# dual_dcdc_converter.net
KiCad netlist of a schematic drawn in EasyEDA Pro
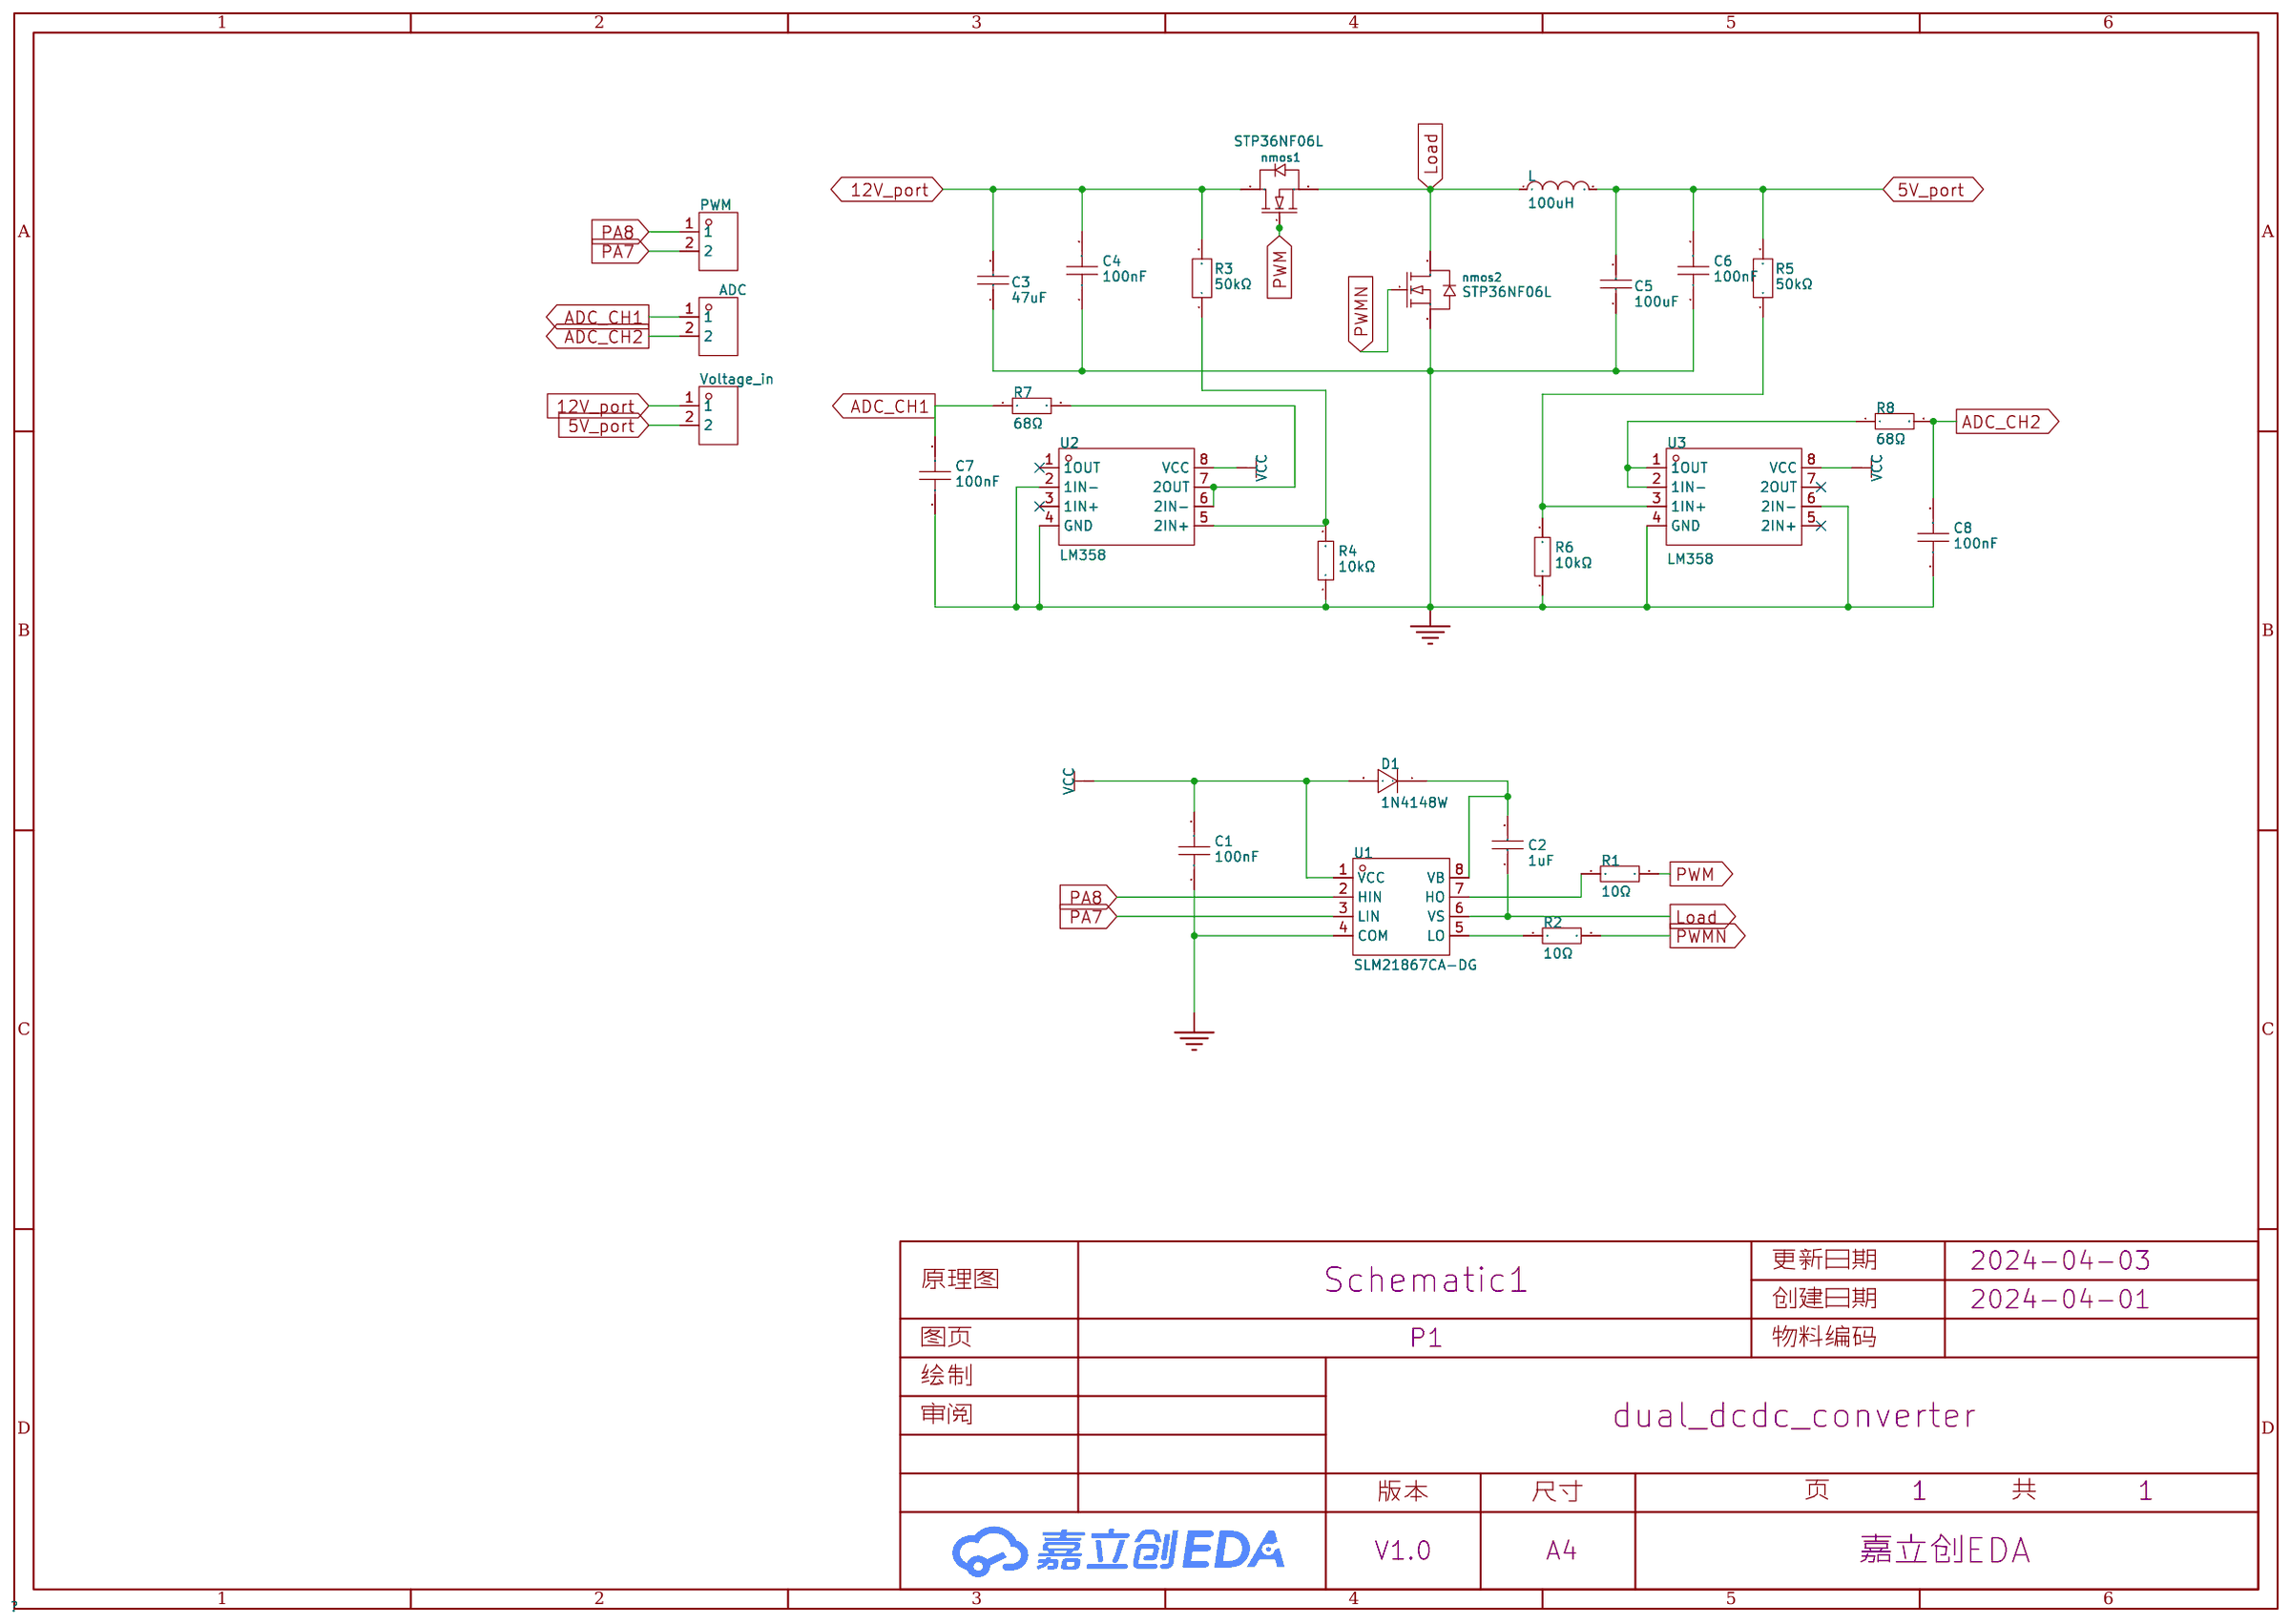
[diagram p0: schematic sheet]

(export (version "E")
  (design (tool "Eeschema 10.0.6"))
  (components
    (comp (ref "ADC")
      (value "FFH25405-S02S1001K6K")
      (footprint "easyedapro:HDR-TH_2P-P2.54-V-F_FFH25405")
      (fields (field (name "Manufacturer") "TXGA(特思嘉)"))
      (libsource (lib "easyedapro") (part "FFH25405-S02S1001K6K"))
    )
    (comp (ref "C1")
      (value "100nF")
      (footprint "easyedapro:C0603")
      (description "容值:100nF;精度:±10%;额定电压:50V;材质(温度系数):X7R;")
      (fields
        (field (name "Manufacturer Part") "CC0603KRX7R9BB104")
        (field (name "Manufacturer") "YAGEO(国巨)")
      )
      (libsource (lib "easyedapro") (part "CC0603KRX7R9BB104"))
    )
    (comp (ref "C2")
      (value "1uF")
      (footprint "easyedapro:C0805")
      (description "容值:1uF;精度:±10%;额定电压:50V;材质(温度系数):X7R;")
      (fields
        (field (name "Manufacturer Part") "CL21B105KBFNNNE")
        (field (name "Manufacturer") "SAMSUNG(三星)")
      )
      (libsource (lib "easyedapro") (part "CL21B105KBFNNNE"))
    )
    (comp (ref "C3")
      (value "47uF")
      (footprint "easyedapro:C0805")
      (description "容值:47uF;精度:±20%;额定电压:6.3V;材质(温度系数):X5R;")
      (fields
        (field (name "Manufacturer Part") "CL21A476MQYNNNE")
        (field (name "Manufacturer") "SAMSUNG(三星)")
      )
      (libsource (lib "easyedapro") (part "CL21A476MQYNNNE"))
    )
    (comp (ref "C4")
      (value "100nF")
      (footprint "easyedapro:C0603")
      (description "容值:100nF;精度:±10%;额定电压:50V;材质(温度系数):X7R;")
      (fields
        (field (name "Manufacturer Part") "CC0603KRX7R9BB104")
        (field (name "Manufacturer") "YAGEO(国巨)")
      )
      (libsource (lib "easyedapro") (part "CC0603KRX7R9BB104"))
    )
    (comp (ref "C5")
      (value "100uF")
      (footprint "easyedapro:C1206")
      (description "容值:100uF;精度:±20%;额定电压:6.3V;材质(温度系数):X5R;")
      (fields
        (field (name "Manufacturer Part") "CL31A107MQHNNNE")
        (field (name "Manufacturer") "SAMSUNG(三星)")
      )
      (libsource (lib "easyedapro") (part "CL31A107MQHNNNE"))
    )
    (comp (ref "C6")
      (value "100nF")
      (footprint "easyedapro:C0603")
      (description "容值:100nF;精度:±10%;额定电压:50V;材质(温度系数):X7R;")
      (fields
        (field (name "Manufacturer Part") "CC0603KRX7R9BB104")
        (field (name "Manufacturer") "YAGEO(国巨)")
      )
      (libsource (lib "easyedapro") (part "CC0603KRX7R9BB104"))
    )
    (comp (ref "C7")
      (value "100nF")
      (footprint "easyedapro:C0603")
      (description "容值:100nF;精度:±10%;额定电压:50V;材质(温度系数):X7R;")
      (fields
        (field (name "Manufacturer Part") "CC0603KRX7R9BB104")
        (field (name "Manufacturer") "YAGEO(国巨)")
      )
      (libsource (lib "easyedapro") (part "CC0603KRX7R9BB104"))
    )
    (comp (ref "C8")
      (value "100nF")
      (footprint "easyedapro:C0603")
      (description "容值:100nF;精度:±10%;额定电压:50V;材质(温度系数):X7R;")
      (fields
        (field (name "Manufacturer Part") "CC0603KRX7R9BB104")
        (field (name "Manufacturer") "YAGEO(国巨)")
      )
      (libsource (lib "easyedapro") (part "CC0603KRX7R9BB104"))
    )
    (comp (ref "D1")
      (value "1N4148W")
      (footprint "easyedapro:SOD-123F_L2.7-W1.6-LS3.8-RD")
      (description "二极管配置:独立式;正向压降(Vf):1V@50mA;直流反向耐压(Vr):75V;平均整流电流(Io):150mA;功率:400mW;反向恢复时间(trr):4ns;")
      (fields (field (name "Manufacturer") "ST(先科)"))
      (libsource (lib "easyedapro") (part "1N4148W_C81598"))
    )
    (comp (ref "L")
      (value "100uH")
      (footprint "easyedapro:IND-SMD_L10.5-W10.5")
      (description "电感值:100uH;精度:±20%;额定电流:1.35A;直流电阻(DCR):340mΩ;")
      (fields (field (name "Manufacturer Part") "CYL104R-100UH") (field (name "Manufacturer") "SHOU HAN(首韩)"))
      (libsource (lib "easyedapro") (part "CYL104R-100UH"))
    )
    (comp (ref "nmos1")
      (value "STP36NF06L")
      (footprint "easyedapro:TO-220-3_L10.0-W4.5-P2.54-L")
      (fields (field (name "Manufacturer") "ST(意法半导体)"))
      (libsource (lib "easyedapro") (part "STP36NF06L"))
    )
    (comp (ref "nmos2")
      (value "STP36NF06L")
      (footprint "easyedapro:TO-220-3_L10.0-W4.5-P2.54-L")
      (fields (field (name "Manufacturer") "ST(意法半导体)"))
      (libsource (lib "easyedapro") (part "STP36NF06L"))
    )
    (comp (ref "PWM")
      (value "FFH25405-S02S1001K6K")
      (footprint "easyedapro:HDR-TH_2P-P2.54-V-F_FFH25405")
      (fields (field (name "Manufacturer") "TXGA(特思嘉)"))
      (libsource (lib "easyedapro") (part "FFH25405-S02S1001K6K"))
    )
    (comp (ref "R1")
      (value "10Ω")
      (footprint "easyedapro:R0603")
      (description "电阻类型:厚膜电阻;阻值:10Ω;精度:±1%;功率:100mW;最大工作电压:75V;温度系数:±400ppm/°C;")
      (fields
        (field (name "Manufacturer Part") "0603WAF100JT5E")
        (field (name "Manufacturer") "UNI-ROYAL(厚声)")
      )
      (libsource (lib "easyedapro") (part "0603WAF100JT5E"))
    )
    (comp (ref "R2")
      (value "10Ω")
      (footprint "easyedapro:R0603")
      (description "电阻类型:厚膜电阻;阻值:10Ω;精度:±1%;功率:100mW;最大工作电压:75V;温度系数:±400ppm/°C;")
      (fields
        (field (name "Manufacturer Part") "0603WAF100JT5E")
        (field (name "Manufacturer") "UNI-ROYAL(厚声)")
      )
      (libsource (lib "easyedapro") (part "0603WAF100JT5E"))
    )
    (comp (ref "R3")
      (value "50kΩ")
      (footprint "easyedapro:R0805")
      (description "电阻类型:薄膜电阻;阻值:50kΩ;精度:±0.5%;功率:125mW;最大工作电压:150V;温度系数:±25ppm/°C;")
      (fields (field (name "Manufacturer Part") "ARG05DTC5002") (field (name "Manufacturer") "Viking(光颉)"))
      (libsource (lib "easyedapro") (part "ARG05DTC5002"))
    )
    (comp (ref "R4")
      (value "10kΩ")
      (footprint "easyedapro:R0603")
      (description "电阻类型:厚膜电阻;阻值:10kΩ;精度:±1%;功率:100mW;最大工作电压:75V;温度系数:±100ppm/°C;")
      (fields
        (field (name "Manufacturer Part") "0603WAF1002T5E")
        (field (name "Manufacturer") "UNI-ROYAL(厚声)")
      )
      (libsource (lib "easyedapro") (part "0603WAF1002T5E"))
    )
    (comp (ref "R5")
      (value "50kΩ")
      (footprint "easyedapro:R0805")
      (description "电阻类型:薄膜电阻;阻值:50kΩ;精度:±0.5%;功率:125mW;最大工作电压:150V;温度系数:±25ppm/°C;")
      (fields (field (name "Manufacturer Part") "ARG05DTC5002") (field (name "Manufacturer") "Viking(光颉)"))
      (libsource (lib "easyedapro") (part "ARG05DTC5002"))
    )
    (comp (ref "R6")
      (value "10kΩ")
      (footprint "easyedapro:R0603")
      (description "电阻类型:厚膜电阻;阻值:10kΩ;精度:±1%;功率:100mW;最大工作电压:75V;温度系数:±100ppm/°C;")
      (fields
        (field (name "Manufacturer Part") "0603WAF1002T5E")
        (field (name "Manufacturer") "UNI-ROYAL(厚声)")
      )
      (libsource (lib "easyedapro") (part "0603WAF1002T5E"))
    )
    (comp (ref "R7")
      (value "68Ω")
      (footprint "easyedapro:R0805")
      (description "电阻类型:厚膜电阻;阻值:68Ω;精度:±1%;功率:125mW;最大工作电压:150V;温度系数:±200ppm/°C;")
      (fields
        (field (name "Manufacturer Part") "0805W8F680JT5E")
        (field (name "Manufacturer") "UNI-ROYAL(厚声)")
      )
      (libsource (lib "easyedapro") (part "0805W8F680JT5E"))
    )
    (comp (ref "R8")
      (value "68Ω")
      (footprint "easyedapro:R0805")
      (description "电阻类型:厚膜电阻;阻值:68Ω;精度:±1%;功率:125mW;最大工作电压:150V;温度系数:±200ppm/°C;")
      (fields
        (field (name "Manufacturer Part") "0805W8F680JT5E")
        (field (name "Manufacturer") "UNI-ROYAL(厚声)")
      )
      (libsource (lib "easyedapro") (part "0805W8F680JT5E"))
    )
    (comp (ref "U1")
      (value "SLM21867CA-DG")
      (footprint "easyedapro:SOIC-8_L4.9-W3.9-P1.27-LS6.0-BL")
      (description "驱动通道数:2;峰值灌电流:2.5A;峰值拉电流:3A;电源电压:7V~20V;是否隔离:非隔离;")
      (fields (field (name "Manufacturer") "Sillumin(数明半导体)"))
      (libsource (lib "easyedapro") (part "SLM21867CA-DG"))
    )
    (comp (ref "U2")
      (value "LM358")
      (footprint "easyedapro:SOP-8_L5.0-W4.0-P1.27-LS6.0-BL")
      (description "放大器数:-;输入失调电压(Vos):9V;带宽(-3db):1MHz;")
      (fields (field (name "Manufacturer") "IDCHIP(英锐芯)"))
      (libsource (lib "easyedapro") (part "LM358_C329455"))
    )
    (comp (ref "U3")
      (value "LM358")
      (footprint "easyedapro:SOP-8_L5.0-W4.0-P1.27-LS6.0-BL")
      (description "放大器数:-;输入失调电压(Vos):9V;带宽(-3db):1MHz;")
      (fields (field (name "Manufacturer") "IDCHIP(英锐芯)"))
      (libsource (lib "easyedapro") (part "LM358_C329455"))
    )
    (comp (ref "Voltage_in")
      (value "FFH25405-S02S1001K6K")
      (footprint "easyedapro:HDR-TH_2P-P2.54-V-F_FFH25405")
      (fields (field (name "Manufacturer") "TXGA(特思嘉)"))
      (libsource (lib "easyedapro") (part "FFH25405-S02S1001K6K"))
    )
  )
  (nets
    (net (code "1") (name "5V_port") (class "Default")
      (node (ref "C5") (pin "2") (pinfunction "2_2") (pintype "input"))
      (node (ref "C6") (pin "2") (pinfunction "2_2") (pintype "unspecified"))
      (node (ref "L") (pin "2") (pinfunction "2_2") (pintype "unspecified"))
      (node (ref "R5") (pin "2") (pinfunction "2_2") (pintype "unspecified"))
      (node (ref "Voltage_in") (pin "2") (pinfunction "2_2") (pintype "unspecified"))
    )
    (net (code "2") (name "12V_port") (class "Default")
      (node (ref "C3") (pin "2") (pinfunction "2_2") (pintype "input"))
      (node (ref "C4") (pin "2") (pinfunction "2_2") (pintype "unspecified"))
      (node (ref "R3") (pin "2") (pinfunction "2_2") (pintype "unspecified"))
      (node (ref "Voltage_in") (pin "1") (pinfunction "1_1") (pintype "unspecified"))
      (node (ref "nmos1") (pin "2") (pinfunction "D_2") (pintype "input"))
    )
    (net (code "3") (name "ADC_CH1") (class "Default")
      (node (ref "ADC") (pin "1") (pinfunction "1_1") (pintype "unspecified"))
      (node (ref "C7") (pin "2") (pinfunction "2_2") (pintype "unspecified"))
      (node (ref "R7") (pin "1") (pinfunction "1_1") (pintype "input"))
    )
    (net (code "4") (name "ADC_CH2") (class "Default")
      (node (ref "ADC") (pin "2") (pinfunction "2_2") (pintype "unspecified"))
      (node (ref "C8") (pin "2") (pinfunction "2_2") (pintype "unspecified"))
      (node (ref "R8") (pin "2") (pinfunction "2_2") (pintype "input"))
    )
    (net (code "5") (name "GND") (class "Default")
      (node (ref "C1") (pin "1") (pinfunction "1_1") (pintype "unspecified"))
      (node (ref "C3") (pin "1") (pinfunction "1_1") (pintype "input"))
      (node (ref "C4") (pin "1") (pinfunction "1_1") (pintype "unspecified"))
      (node (ref "C5") (pin "1") (pinfunction "1_1") (pintype "input"))
      (node (ref "C6") (pin "1") (pinfunction "1_1") (pintype "unspecified"))
      (node (ref "C7") (pin "1") (pinfunction "1_1") (pintype "unspecified"))
      (node (ref "C8") (pin "1") (pinfunction "1_1") (pintype "unspecified"))
      (node (ref "R4") (pin "1") (pinfunction "1_1") (pintype "input"))
      (node (ref "R6") (pin "1") (pinfunction "1_1") (pintype "input"))
      (node (ref "U1") (pin "4") (pinfunction "COM_4") (pintype "input"))
      (node (ref "U2") (pin "2") (pinfunction "1IN-_2") (pintype "unspecified"))
      (node (ref "U2") (pin "4") (pinfunction "GND_4") (pintype "unspecified"))
      (node (ref "U3") (pin "4") (pinfunction "GND_4") (pintype "unspecified"))
      (node (ref "U3") (pin "6") (pinfunction "2IN-_6") (pintype "unspecified"))
      (node (ref "nmos2") (pin "3") (pinfunction "S_3") (pintype "input"))
    )
    (net (code "6") (name "Load") (class "Default")
      (node (ref "C2") (pin "1") (pinfunction "1_1") (pintype "input"))
      (node (ref "L") (pin "1") (pinfunction "1_1") (pintype "unspecified"))
      (node (ref "U1") (pin "6") (pinfunction "VS_6") (pintype "input"))
      (node (ref "nmos1") (pin "3") (pinfunction "S_3") (pintype "input"))
      (node (ref "nmos2") (pin "2") (pinfunction "D_2") (pintype "input"))
    )
    (net (code "7") (name "Net-(D1-K)") (class "Default")
      (node (ref "C2") (pin "2") (pinfunction "2_2") (pintype "input"))
      (node (ref "D1") (pin "1") (pinfunction "K_1") (pintype "unspecified"))
      (node (ref "U1") (pin "8") (pinfunction "VB_8") (pintype "input"))
    )
    (net (code "8") (name "Net-(U1-HO)") (class "Default")
      (node (ref "R1") (pin "1") (pinfunction "1_1") (pintype "input"))
      (node (ref "U1") (pin "7") (pinfunction "HO_7") (pintype "input"))
    )
    (net (code "9") (name "Net-(U1-LO)") (class "Default")
      (node (ref "R2") (pin "1") (pinfunction "1_1") (pintype "input"))
      (node (ref "U1") (pin "5") (pinfunction "LO_5") (pintype "input"))
    )
    (net (code "10") (name "Net-(U2-2IN+)") (class "Default")
      (node (ref "R3") (pin "1") (pinfunction "1_1") (pintype "unspecified"))
      (node (ref "R4") (pin "2") (pinfunction "2_2") (pintype "input"))
      (node (ref "U2") (pin "5") (pinfunction "2IN+_5") (pintype "unspecified"))
    )
    (net (code "11") (name "Net-(U2-2IN-)") (class "Default")
      (node (ref "R7") (pin "2") (pinfunction "2_2") (pintype "input"))
      (node (ref "U2") (pin "6") (pinfunction "2IN-_6") (pintype "unspecified"))
      (node (ref "U2") (pin "7") (pinfunction "2OUT_7") (pintype "unspecified"))
    )
    (net (code "12") (name "Net-(U3-1IN+)") (class "Default")
      (node (ref "R5") (pin "1") (pinfunction "1_1") (pintype "unspecified"))
      (node (ref "R6") (pin "2") (pinfunction "2_2") (pintype "input"))
      (node (ref "U3") (pin "3") (pinfunction "1IN+_3") (pintype "unspecified"))
    )
    (net (code "13") (name "Net-(U3-1IN-)") (class "Default")
      (node (ref "R8") (pin "1") (pinfunction "1_1") (pintype "input"))
      (node (ref "U3") (pin "1") (pinfunction "1OUT_1") (pintype "unspecified"))
      (node (ref "U3") (pin "2") (pinfunction "1IN-_2") (pintype "unspecified"))
    )
    (net (code "14") (name "PA7") (class "Default")
      (node (ref "PWM") (pin "2") (pinfunction "2_2") (pintype "unspecified"))
      (node (ref "U1") (pin "3") (pinfunction "LIN_3") (pintype "input"))
    )
    (net (code "15") (name "PA8") (class "Default")
      (node (ref "PWM") (pin "1") (pinfunction "1_1") (pintype "unspecified"))
      (node (ref "U1") (pin "2") (pinfunction "HIN_2") (pintype "input"))
    )
    (net (code "16") (name "PWM") (class "Default")
      (node (ref "R1") (pin "2") (pinfunction "2_2") (pintype "input"))
      (node (ref "nmos1") (pin "1") (pinfunction "G_1") (pintype "input"))
    )
    (net (code "17") (name "PWMN") (class "Default")
      (node (ref "R2") (pin "2") (pinfunction "2_2") (pintype "input"))
      (node (ref "nmos2") (pin "1") (pinfunction "G_1") (pintype "input"))
    )
    (net (code "18") (name "VCC") (class "Default")
      (node (ref "C1") (pin "2") (pinfunction "2_2") (pintype "unspecified"))
      (node (ref "D1") (pin "2") (pinfunction "A_2") (pintype "unspecified"))
      (node (ref "U1") (pin "1") (pinfunction "VCC_1") (pintype "input"))
      (node (ref "U2") (pin "8") (pinfunction "VCC_8") (pintype "unspecified"))
      (node (ref "U3") (pin "8") (pinfunction "VCC_8") (pintype "unspecified"))
    )
    (net (code "19") (name "unconnected-(U2-1IN+-Pad3)") (class "Default")
      (node (ref "U2") (pin "3") (pinfunction "1IN+_3") (pintype "unspecified+no_connect"))
    )
    (net (code "20") (name "unconnected-(U2-1OUT-Pad1)") (class "Default")
      (node (ref "U2") (pin "1") (pinfunction "1OUT_1") (pintype "unspecified+no_connect"))
    )
    (net (code "21") (name "unconnected-(U3-2IN+-Pad5)") (class "Default")
      (node (ref "U3") (pin "5") (pinfunction "2IN+_5") (pintype "unspecified+no_connect"))
    )
    (net (code "22") (name "unconnected-(U3-2OUT-Pad7)") (class "Default")
      (node (ref "U3") (pin "7") (pinfunction "2OUT_7") (pintype "unspecified+no_connect"))
    )
  )
)
